# Isolated-ARD-Channel.net
KiCad netlist of a schematic drawn in EAGLE
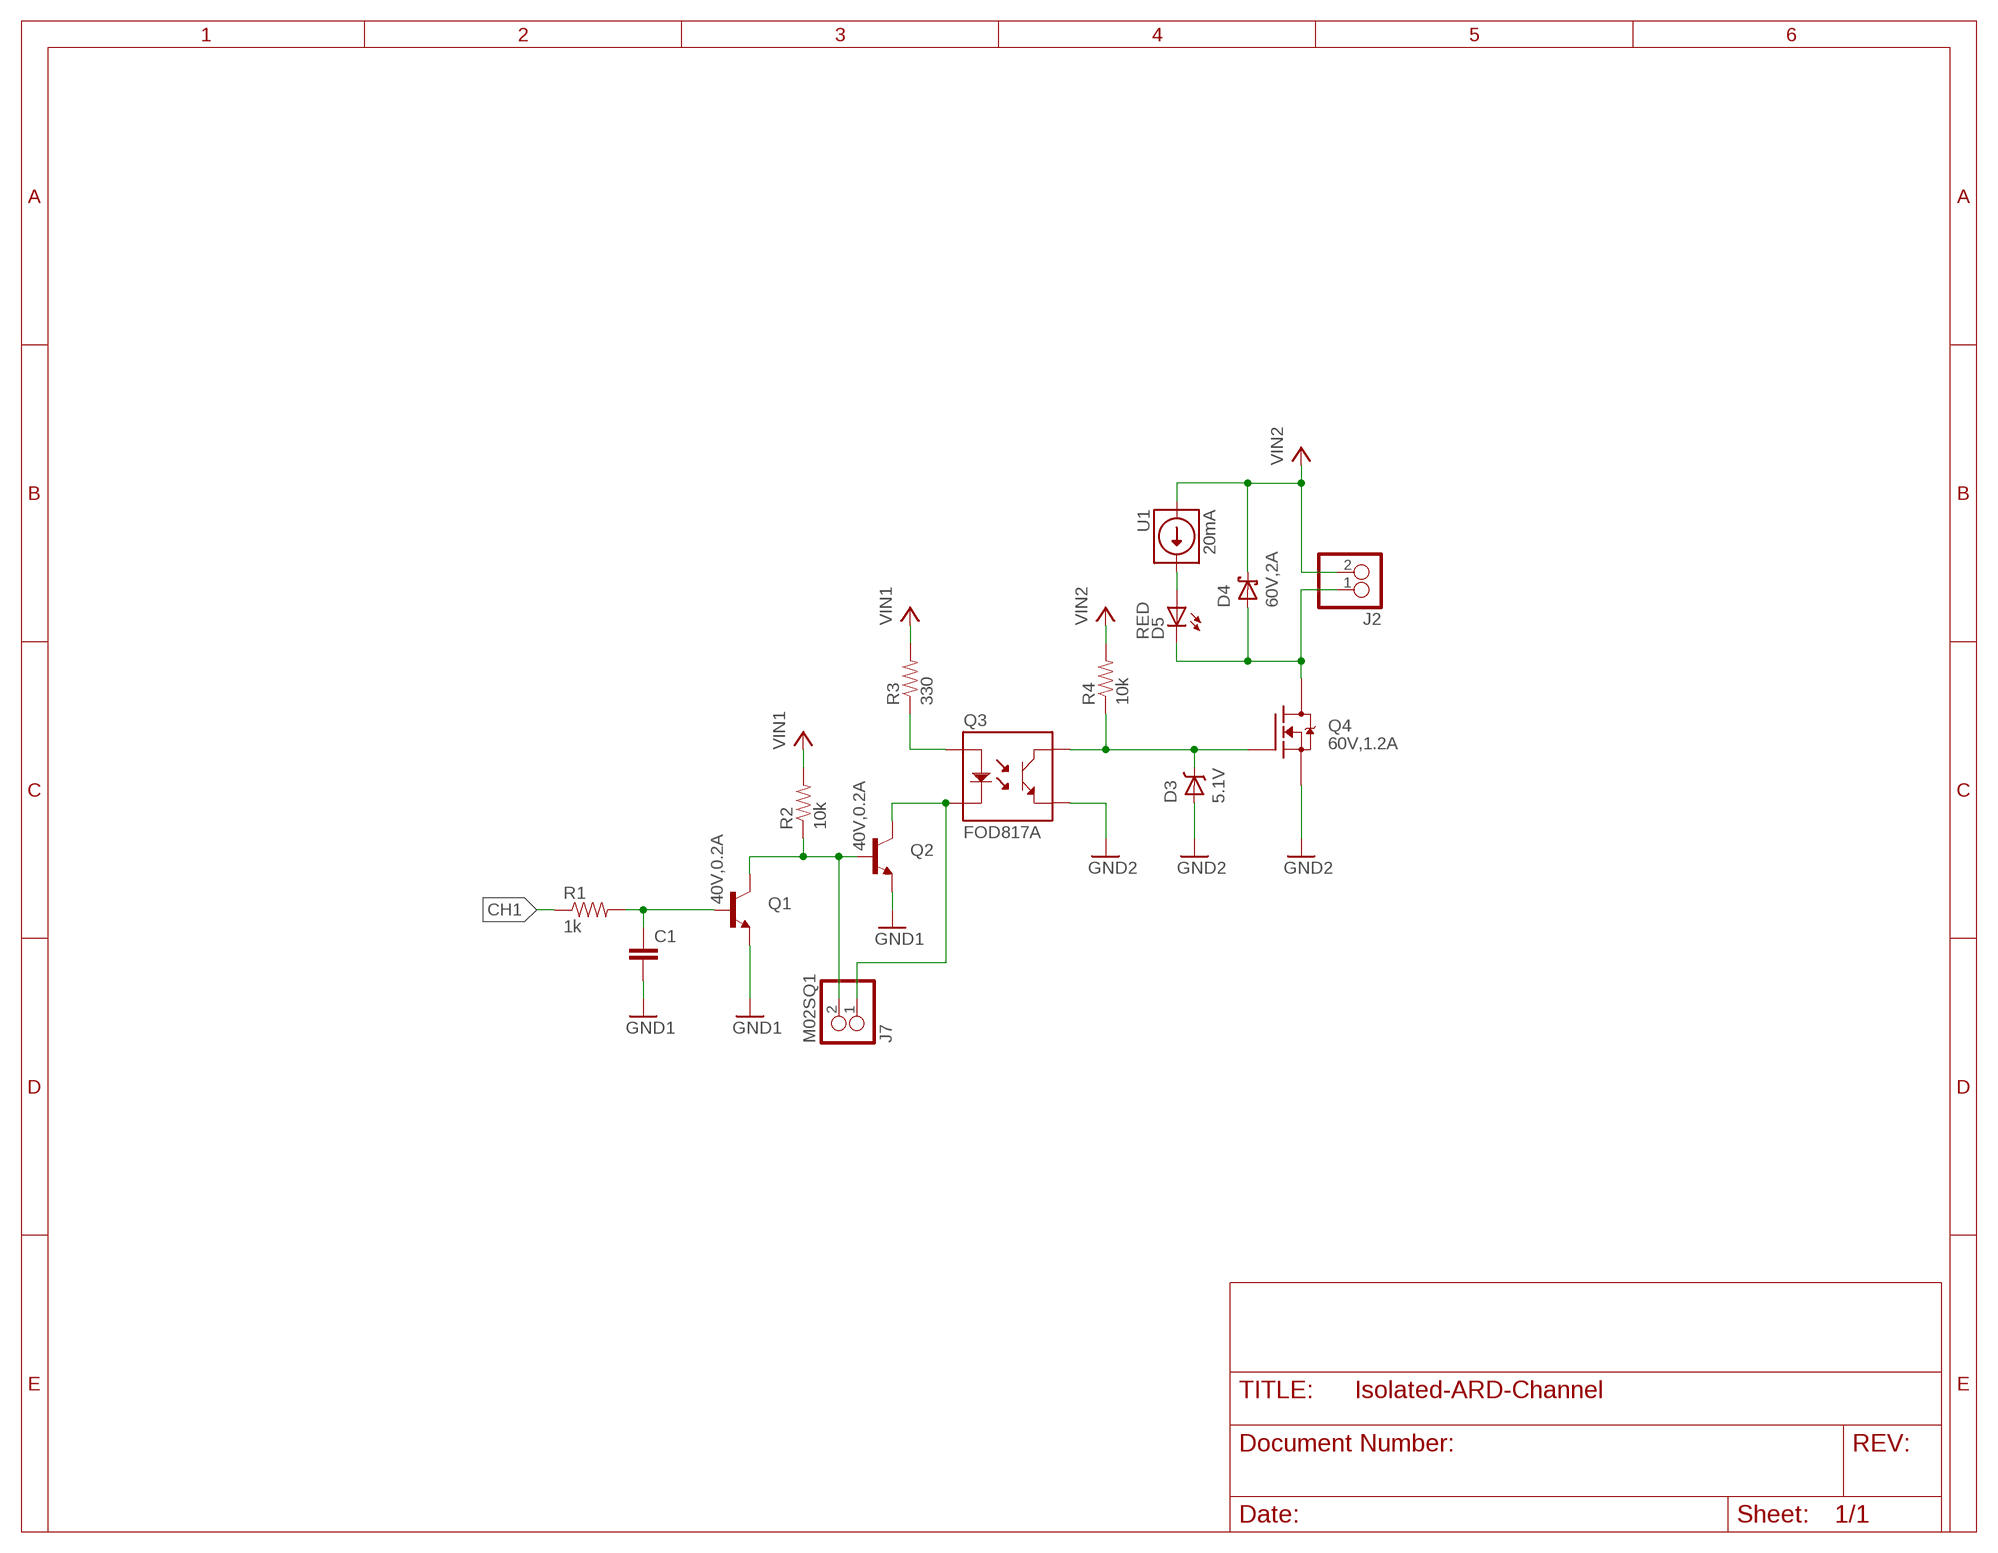
[diagram p0: schematic, sheet 1]

(export (version "E")
  (design (tool "Eeschema 10.0.6"))
  (components
    (comp (ref "C1")
      (value "C-0805")
      (footprint "eagle-import:0805-CAP")
      (libsource (lib "eagle-import") (part "C-0805"))
    )
    (comp (ref "D3")
      (value "5.1V")
      (footprint "eagle-import:SOD-123")
      (fields (field (name "MFR") "Diodes Incorporated") (field (name "MPN") "MMSZ5231B-7-F"))
      (libsource (lib "eagle-import") (part "MMSZ52B?-7-F31"))
    )
    (comp (ref "D4")
      (value "60V,2A")
      (footprint "eagle-import:SMA-DIODE")
      (fields (field (name "MFR") "Diodes Incorporated") (field (name "MPN") "B260A-13-F"))
      (libsource (lib "eagle-import") (part "B2A-13-F60"))
    )
    (comp (ref "D5")
      (value "RED")
      (footprint "eagle-import:1206-LED")
      (fields (field (name "MFR") "Lite-On Inc.") (field (name "MPN") "LTST-C150KRKT"))
      (libsource (lib "eagle-import") (part "LTST-C?KKT150R"))
    )
    (comp (ref "J2")
      (value "M02SKT-3.5MM-R90")
      (footprint "eagle-import:SOCKET-3.5MM-2-R90")
      (libsource (lib "eagle-import") (part "M02?SKT-3.5MM-R90"))
    )
    (comp (ref "J7")
      (value "M02SQ1")
      (footprint "eagle-import:1X02_SQ1")
      (libsource (lib "eagle-import") (part "M02?SQ1"))
    )
    (comp (ref "Q1")
      (value "40V,0.2A")
      (footprint "eagle-import:SOT23-3")
      (fields (field (name "MFR") "Diodes Incorporated") (field (name "MPN") "MMBT3904-7-F"))
      (libsource (lib "eagle-import") (part "MMBT3904"))
    )
    (comp (ref "Q2")
      (value "40V,0.2A")
      (footprint "eagle-import:SOT23-3")
      (fields (field (name "MFR") "Diodes Incorporated") (field (name "MPN") "MMBT3904-7-F"))
      (libsource (lib "eagle-import") (part "MMBT3904"))
    )
    (comp (ref "Q3")
      (value "FOD817A")
      (footprint "eagle-import:4-SMD")
      (fields (field (name "MFR") "Fairchild Semiconductor") (field (name "MPN") "FOD817DSD"))
      (libsource (lib "eagle-import") (part "FOD817A"))
    )
    (comp (ref "Q4")
      (value "60V,1.2A")
      (footprint "eagle-import:SOT23-3")
      (fields (field (name "MFR") "International Rectifier") (field (name "MPN") "IRLML2060TRPBF"))
      (libsource (lib "eagle-import") (part "IRLML2060TRPBF"))
    )
    (comp (ref "R1")
      (value "1k")
      (footprint "eagle-import:0805-RES")
      (fields
        (field (name "MFR") "Panasonic Electronic Components")
        (field (name "MPN") "ERJ-6GEYJ102V")
        (field (name "POWER") "0.125W")
      )
      (libsource (lib "eagle-import") (part "1K--?08055%"))
    )
    (comp (ref "R2")
      (value "10k")
      (footprint "eagle-import:0805-RES")
      (fields
        (field (name "MFR") "Panasonic Electronic Components")
        (field (name "MPN") "ERJ-6GEYJ103V")
        (field (name "POWER") "0.125W")
      )
      (libsource (lib "eagle-import") (part "10K--?08055%"))
    )
    (comp (ref "R3")
      (value "330")
      (footprint "eagle-import:0805-RES")
      (fields
        (field (name "MFR") "Panasonic Electronic Components")
        (field (name "MPN") "ERJ-6GEYJ331V")
        (field (name "POWER") "0.125W")
      )
      (libsource (lib "eagle-import") (part "330--?08055%"))
    )
    (comp (ref "R4")
      (value "10k")
      (footprint "eagle-import:0805-RES")
      (fields
        (field (name "MFR") "Panasonic Electronic Components")
        (field (name "MPN") "ERJ-6GEYJ103V")
        (field (name "POWER") "0.125W")
        (field (name "DESC") "RES 10K OHM 1/8W 5% 0805 SMD")
        (field (name "DIGIKEY_OC") "P10KACT-ND")
        (field (name "MFR_1") "Panasonic Electronic Components")
        (field (name "MPN_1") "ERJ-6GEYJ103V")
        (field (name "POWER_1") "0.125W")
      )
      (libsource (lib "eagle-import") (part "10K--?08055%"))
    )
    (comp (ref "U1")
      (value "20mA")
      (footprint "eagle-import:SOD-123")
      (fields (field (name "MFR") "ON Semiconductor") (field (name "MPN") "NSI45020T1G"))
      (libsource (lib "eagle-import") (part "NSI45020T1G"))
    )
  )
  (nets
    (net (code "1") (name "CH1") (class "Default")
      (node (ref "R1") (pin "P$1") (pinfunction "1_P$1") (pintype "passive"))
    )
    (net (code "2") (name "GND1") (class "Default")
      (node (ref "C1") (pin "P$2") (pinfunction "2_P$2") (pintype "passive"))
      (node (ref "Q1") (pin "2") (pinfunction "E_2") (pintype "passive"))
      (node (ref "Q2") (pin "2") (pinfunction "E_2") (pintype "passive"))
    )
    (net (code "3") (name "GND2") (class "Default")
      (node (ref "D3") (pin "A") (pinfunction "A_A") (pintype "passive"))
      (node (ref "Q3") (pin "3") (pinfunction "T_E_3") (pintype "bidirectional"))
      (node (ref "Q4") (pin "2") (pinfunction "S_2") (pintype "passive"))
    )
    (net (code "4") (name "Net-(C1-1)") (class "Default")
      (node (ref "C1") (pin "P$1") (pinfunction "1_P$1") (pintype "passive"))
      (node (ref "Q1") (pin "1") (pinfunction "B_1") (pintype "passive"))
      (node (ref "R1") (pin "P$2") (pinfunction "2_P$2") (pintype "passive"))
    )
    (net (code "5") (name "Net-(D5-PadA)") (class "Default")
      (node (ref "D5") (pin "A") (pinfunction "A_A") (pintype "passive"))
      (node (ref "U1") (pin "C") (pinfunction "C_C") (pintype "bidirectional"))
    )
    (net (code "6") (name "Net-(Q1-C)") (class "Default")
      (node (ref "J7") (pin "2") (pinfunction "2_2") (pintype "bidirectional"))
      (node (ref "Q1") (pin "3") (pinfunction "C_3") (pintype "passive"))
      (node (ref "Q2") (pin "1") (pinfunction "B_1") (pintype "passive"))
      (node (ref "R2") (pin "P$1") (pinfunction "1_P$1") (pintype "passive"))
    )
    (net (code "7") (name "Net-(Q2-C)") (class "Default")
      (node (ref "J7") (pin "1") (pinfunction "1_1") (pintype "bidirectional"))
      (node (ref "Q2") (pin "3") (pinfunction "C_3") (pintype "passive"))
      (node (ref "Q3") (pin "2") (pinfunction "LED_C_2") (pintype "bidirectional"))
    )
    (net (code "8") (name "Net-(Q3-LED_A)") (class "Default")
      (node (ref "Q3") (pin "1") (pinfunction "LED_A_1") (pintype "bidirectional"))
      (node (ref "R3") (pin "P$1") (pinfunction "1_P$1") (pintype "passive"))
    )
    (net (code "9") (name "Net-(Q3-T_C)") (class "Default")
      (node (ref "D3") (pin "C") (pinfunction "C_C") (pintype "passive"))
      (node (ref "Q3") (pin "4") (pinfunction "T_C_4") (pintype "bidirectional"))
      (node (ref "Q4") (pin "1") (pinfunction "G_1") (pintype "passive"))
      (node (ref "R4") (pin "P$1") (pinfunction "1_P$1") (pintype "passive"))
    )
    (net (code "10") (name "Net-(Q4-D)") (class "Default")
      (node (ref "D4") (pin "A") (pinfunction "A_A") (pintype "passive"))
      (node (ref "D5") (pin "C") (pinfunction "C_C") (pintype "passive"))
      (node (ref "J2") (pin "1") (pinfunction "1_1") (pintype "bidirectional"))
      (node (ref "Q4") (pin "3") (pinfunction "D_3") (pintype "passive"))
    )
    (net (code "11") (name "VIN1") (class "Default")
      (node (ref "R2") (pin "P$2") (pinfunction "2_P$2") (pintype "passive"))
      (node (ref "R3") (pin "P$2") (pinfunction "2_P$2") (pintype "passive"))
    )
    (net (code "12") (name "VIN2") (class "Default")
      (node (ref "D4") (pin "C") (pinfunction "C_C") (pintype "passive"))
      (node (ref "J2") (pin "2") (pinfunction "2_2") (pintype "bidirectional"))
      (node (ref "R4") (pin "P$2") (pinfunction "2_P$2") (pintype "passive"))
      (node (ref "U1") (pin "A") (pinfunction "A_A") (pintype "bidirectional"))
    )
  )
)
